# pixracer_imu.net
KiCad netlist of a schematic drawn in Altium Designer
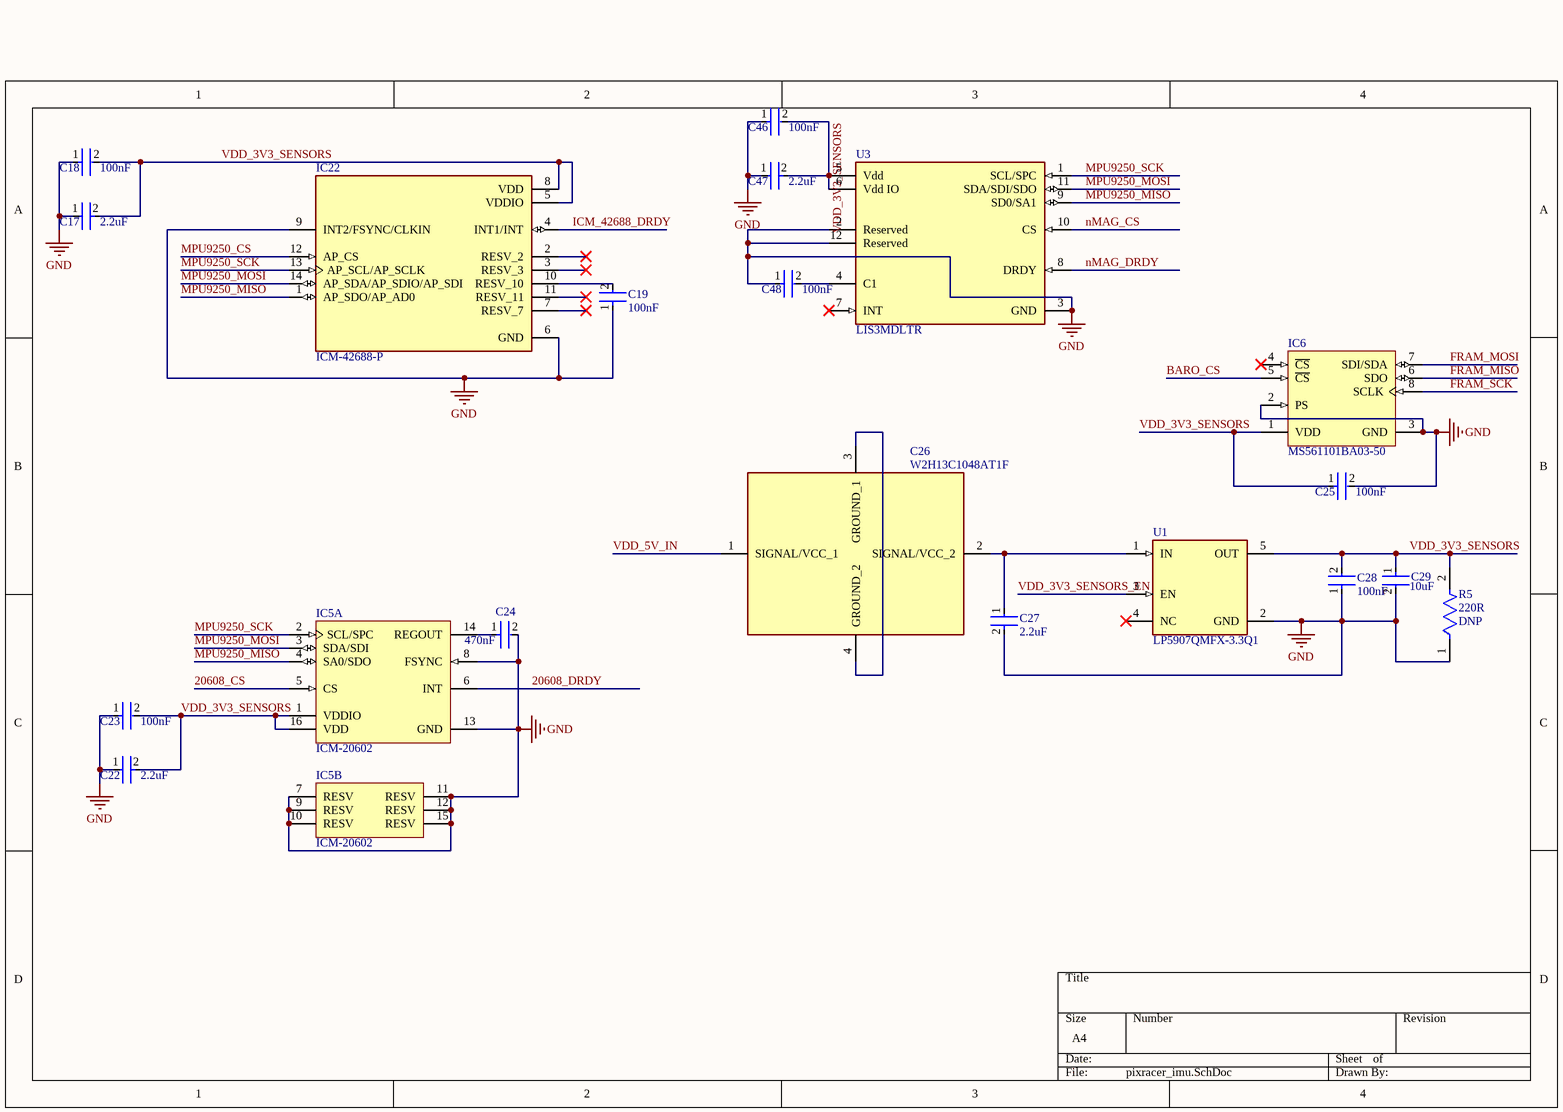
[diagram p0: pixracer_imu.SchDoc]

(export (version "E")
  (design (tool "Eeschema 10.0.6"))
  (components
    (comp (ref "C17")
      (value "C1608X7R1A225K080AC")
      (footprint "FP-C1608-080-0_1-MFG")
      (description "Multilayer Ceramic Capacitors 2.2μF ±10% 10V X7R SMD 0603")
      (fields (field (name "CAPACITANCE") "2.2uF") (field (name "TOLERANCE") "10%"))
      (libsource (lib "Altium Content Vault") (part "236180d848d6139a670b325ea6854c9"))
    )
    (comp (ref "C18")
      (value "0603ZC104MAT2A")
      (footprint "FP-0603-L_1_6_0_15-W_0_81-IPC_B")
      (description "General Purpose Ceramic Capacitor, 0603, 100nF, 20%, X7R, 15%, 10V")
      (fields (field (name "TOLERANCE") "20%") (field (name "CAPACITANCE") "100nF"))
      (libsource (lib "Altium Content Vault") (part "02cd4be3c70576c341d710602a673aa"))
    )
    (comp (ref "C19")
      (value "0603ZC104MAT2A")
      (footprint "FP-0603-L_1_6_0_15-W_0_81-IPC_B")
      (description "General Purpose Ceramic Capacitor, 0603, 100nF, 20%, X7R, 15%, 10V")
      (fields (field (name "TOLERANCE") "20%") (field (name "CAPACITANCE") "100nF"))
      (libsource (lib "Altium Content Vault") (part "02cd4be3c70576c341d710602a673aa"))
    )
    (comp (ref "C22")
      (value "C1608X7R1A225K080AC")
      (footprint "FP-C1608-080-0_1-MFG")
      (description "Multilayer Ceramic Capacitors 2.2μF ±10% 10V X7R SMD 0603")
      (fields (field (name "CAPACITANCE") "2.2uF") (field (name "TOLERANCE") "10%"))
      (libsource (lib "Altium Content Vault") (part "236180d848d6139a670b325ea6854c9"))
    )
    (comp (ref "C23")
      (value "0603ZC104MAT2A")
      (footprint "FP-0603-L_1_6_0_15-W_0_81-IPC_B")
      (description "General Purpose Ceramic Capacitor, 0603, 100nF, 20%, X7R, 15%, 10V")
      (fields (field (name "TOLERANCE") "20%") (field (name "CAPACITANCE") "100nF"))
      (libsource (lib "Altium Content Vault") (part "02cd4be3c70576c341d710602a673aa"))
    )
    (comp (ref "C24")
      (value "CL10B474KP8NNNC")
      (footprint "FP-CL10-IPC_B")
      (description "Cap Ceramic 470nF 10V X7R ±10% Pad SMD 0603 +125°C T/R")
      (fields
        (field (name "VOLTAGE") "10V")
        (field (name "CAPACITANCE") "470nF")
        (field (name "TOLERANCE") "10%")
      )
      (libsource (lib "Altium Content Vault") (part "b4654b650e69147ec39a6b967a45e02"))
    )
    (comp (ref "C25")
      (value "0603ZC104MAT2A")
      (footprint "FP-0603-L_1_6_0_15-W_0_81-IPC_B")
      (description "General Purpose Ceramic Capacitor, 0603, 100nF, 20%, X7R, 15%, 10V")
      (fields (field (name "TOLERANCE") "20%") (field (name "CAPACITANCE") "100nF"))
      (libsource (lib "Altium Content Vault") (part "02cd4be3c70576c341d710602a673aa"))
    )
    (comp (ref "C26")
      (value "W2H13C1048AT1F")
      (footprint "SamacSys:W2H13C1048AT1A")
      (description "Capacitor")
      (fields (field (name "MOUSER PART NUMBER") "581-W2H13C1048AT1F"))
      (libsource (lib "*") (part "W2H13C1048AT1F"))
    )
    (comp (ref "C27")
      (value "C1608X7R1A225K080AC")
      (footprint "FP-C1608-080-0_1-MFG")
      (description "Multilayer Ceramic Capacitors 2.2μF ±10% 10V X7R SMD 0603")
      (fields (field (name "CAPACITANCE") "2.2uF") (field (name "TOLERANCE") "10%"))
      (libsource (lib "Altium Content Vault") (part "236180d848d6139a670b325ea6854c9"))
    )
    (comp (ref "C28")
      (value "0603ZC104MAT2A")
      (footprint "FP-0603-L_1_6_0_15-W_0_81-IPC_B")
      (description "General Purpose Ceramic Capacitor, 0603, 100nF, 20%, X7R, 15%, 10V")
      (fields (field (name "TOLERANCE") "20%") (field (name "CAPACITANCE") "100nF"))
      (libsource (lib "Altium Content Vault") (part "02cd4be3c70576c341d710602a673aa"))
    )
    (comp (ref "C29")
      (value "CL10A106KP8NNND")
      (footprint "FP-CL10-IPC_B")
      (description "Cap Ceramic 10uF 10V X5R ±10% Pad SMD 0603 +85°C T/R")
      (fields (field (name "TOLERANCE") "10%") (field (name "CAPACITANCE") "10uF"))
      (libsource (lib "Altium Content Vault") (part "b4654b650e69147ec39a6b967a45e02"))
    )
    (comp (ref "C46")
      (value "0603ZC104MAT2A")
      (footprint "FP-0603-L_1_6_0_15-W_0_81-IPC_B")
      (description "General Purpose Ceramic Capacitor, 0603, 100nF, 20%, X7R, 15%, 10V")
      (fields (field (name "TOLERANCE") "20%") (field (name "CAPACITANCE") "100nF"))
      (libsource (lib "Altium Content Vault") (part "02cd4be3c70576c341d710602a673aa"))
    )
    (comp (ref "C47")
      (value "C1608X7R1A225K080AC")
      (footprint "FP-C1608-080-0_1-MFG")
      (description "Multilayer Ceramic Capacitors 2.2μF ±10% 10V X7R SMD 0603")
      (fields (field (name "CAPACITANCE") "2.2uF") (field (name "TOLERANCE") "10%"))
      (libsource (lib "Altium Content Vault") (part "236180d848d6139a670b325ea6854c9"))
    )
    (comp (ref "C48")
      (value "0603ZC104MAT2A")
      (footprint "FP-0603-L_1_6_0_15-W_0_81-IPC_B")
      (description "General Purpose Ceramic Capacitor, 0603, 100nF, 20%, X7R, 15%, 10V")
      (fields (field (name "TOLERANCE") "20%") (field (name "CAPACITANCE") "100nF"))
      (libsource (lib "Altium Content Vault") (part "02cd4be3c70576c341d710602a673aa"))
    )
    (comp (ref "IC5")
      (value "ICM-20602")
      (footprint "INSE-I62-16")
      (fields (field (name "MANUFACTURER") "InvenSense"))
      (libsource (lib "Altium Content Vault") (part "INSE-ICM-20602-16"))
    )
    (comp (ref "IC6")
      (value "MS561101BA03-50")
      (footprint "MSI-MS561101BA03-50-8_V")
      (fields (field (name "MANUFACTURER") "Measurement Specialties"))
      (libsource (lib "Altium Content Vault") (part "MSI-MS561101BA03-50-8"))
    )
    (comp (ref "IC22")
      (value "ICM-42688-P")
      (footprint "PQFN50P300X250X97-14N")
      (description "Accelerometer, Gyroscope, 6 Axis Sensor Output")
      (libsource (lib "ICM-42688-P") (part "ICM-42688-P"))
    )
    (comp (ref "R5")
      (value "DNP")
      (footprint "FP-CRCW0603-e3-MFG")
      (description "RES Thick Film, 220Ω, 1%, 0.1W, 100ppm/°C, 0603")
      (fields (field (name "TOLERANCE") "1%") (field (name "RESISTANCE") "220R"))
      (libsource (lib "Altium Content Vault") (part "1029c3af85768c4190bb7ad29bc67b5"))
    )
    (comp (ref "U1")
      (value "LP5907QMFX-3.3Q1")
      (footprint "FP-DBV0005A-MFG")
      (description "IC REG LINEAR 3.3V 250MA SOT23-5")
      (fields
        (field (name "MANUFACTURER") "Texas Instruments")
        (field (name "OCTOPART") "https://octopart.com/lp5907qmfx-3.3q1-texas+instruments-50417899")
      )
      (libsource (lib "Altium Content Vault") (part "e6eddeb8bab6a4ee265087e5808ab9f"))
    )
    (comp (ref "U3")
      (value "LIS3MDLTR")
      (footprint "FP-VFLGA-12-8365767-MFG")
      (description "SENSOR MR I2C/SPI 12LGA")
      (fields
        (field (name "OCTOPART") "https://octopart.com/lis3mdltr-stmicroelectronics-29403125")
        (field (name "MANUFACTURER") "STMicroelectronics")
      )
      (libsource (lib "Altium Content Vault") (part "41c0331d4207a07573b21020ef49d7d"))
    )
  )
  (nets
    (net (code "1") (name "/20608_CS") (class "Default")
      (node (ref "IC5") (pin "5") (pinfunction "CS_5") (pintype "input"))
    )
    (net (code "2") (name "/20608_DRDY") (class "Default")
      (node (ref "IC5") (pin "6") (pinfunction "INT_6") (pintype "open_collector"))
    )
    (net (code "3") (name "/BARO_CS") (class "Default")
      (node (ref "IC6") (pin "5") (pinfunction "~{CS}_5") (pintype "input"))
    )
    (net (code "4") (name "/FRAM_MISO") (class "Default")
      (node (ref "IC6") (pin "6") (pinfunction "SDO_6") (pintype "bidirectional"))
    )
    (net (code "5") (name "/FRAM_MOSI") (class "Default")
      (node (ref "IC6") (pin "7") (pinfunction "SDI/SDA_7") (pintype "bidirectional"))
    )
    (net (code "6") (name "/FRAM_SCK") (class "Default")
      (node (ref "IC6") (pin "8") (pinfunction "SCLK_8") (pintype "input"))
    )
    (net (code "7") (name "/ICM_42688_DRDY") (class "Default")
      (node (ref "IC22") (pin "4") (pinfunction "INT1/INT_4") (pintype "bidirectional"))
    )
    (net (code "8") (name "/MPU9250_CS") (class "Default")
      (node (ref "IC22") (pin "12") (pinfunction "AP_CS_12") (pintype "input"))
    )
    (net (code "9") (name "/MPU9250_MISO") (class "Default")
      (node (ref "IC22") (pin "1") (pinfunction "AP_SDO/AP_AD0_1") (pintype "bidirectional"))
      (node (ref "IC5") (pin "4") (pinfunction "SA0/SDO_4") (pintype "bidirectional"))
      (node (ref "U3") (pin "9") (pinfunction "SD0/SA1_9") (pintype "bidirectional"))
    )
    (net (code "10") (name "/MPU9250_MOSI") (class "Default")
      (node (ref "IC22") (pin "14") (pinfunction "AP_SDA/AP_SDIO/AP_SDI_14") (pintype "bidirectional"))
      (node (ref "IC5") (pin "3") (pinfunction "SDA/SDI_3") (pintype "bidirectional"))
      (node (ref "U3") (pin "11") (pinfunction "SDA/SDI/SDO_11") (pintype "bidirectional"))
    )
    (net (code "11") (name "/MPU9250_SCK") (class "Default")
      (node (ref "IC22") (pin "13") (pinfunction "AP_SCL/AP_SCLK_13") (pintype "input"))
      (node (ref "IC5") (pin "2") (pinfunction "SCL/SPC_2") (pintype "input"))
      (node (ref "U3") (pin "1") (pinfunction "SCL/SPC_1") (pintype "input"))
    )
    (net (code "12") (name "/VDD_3V3_SENSORS") (class "Default")
      (node (ref "C17") (pin "2") (pinfunction "2_2") (pintype "passive"))
      (node (ref "C18") (pin "2") (pinfunction "2_2") (pintype "passive"))
      (node (ref "C22") (pin "2") (pinfunction "2_2") (pintype "passive"))
      (node (ref "C23") (pin "2") (pinfunction "2_2") (pintype "passive"))
      (node (ref "C25") (pin "1") (pinfunction "1_1") (pintype "passive"))
      (node (ref "C28") (pin "2") (pinfunction "2_2") (pintype "passive"))
      (node (ref "C29") (pin "1") (pinfunction "1_1") (pintype "passive"))
      (node (ref "C46") (pin "2") (pinfunction "2_2") (pintype "passive"))
      (node (ref "C47") (pin "2") (pinfunction "2_2") (pintype "passive"))
      (node (ref "IC22") (pin "5") (pinfunction "VDDIO_5") (pintype "passive"))
      (node (ref "IC22") (pin "8") (pinfunction "VDD_8") (pintype "passive"))
      (node (ref "IC5") (pin "1") (pinfunction "VDDIO_1") (pintype "power_in"))
      (node (ref "IC5") (pin "16") (pinfunction "VDD_16") (pintype "power_in"))
      (node (ref "IC6") (pin "1") (pinfunction "VDD_1") (pintype "power_in"))
      (node (ref "R5") (pin "2") (pinfunction "2_2") (pintype "passive"))
      (node (ref "U1") (pin "5") (pinfunction "OUT_5") (pintype "power_in"))
      (node (ref "U3") (pin "5") (pinfunction "Vdd_5") (pintype "power_in"))
      (node (ref "U3") (pin "6") (pinfunction "Vdd_IO_6") (pintype "power_in"))
    )
    (net (code "13") (name "/VDD_3V3_SENSORS_EN") (class "Default")
      (node (ref "U1") (pin "3") (pinfunction "EN_3") (pintype "input"))
    )
    (net (code "14") (name "/VDD_5V_IN") (class "Default")
      (node (ref "C26") (pin "1") (pinfunction "SIGNAL/VCC_1_1") (pintype "passive"))
    )
    (net (code "15") (name "/nMAG_CS") (class "Default")
      (node (ref "U3") (pin "10") (pinfunction "CS_10") (pintype "input"))
    )
    (net (code "16") (name "/nMAG_DRDY") (class "Default")
      (node (ref "U3") (pin "8") (pinfunction "DRDY_8") (pintype "input"))
    )
    (net (code "17") (name "GND") (class "Default")
      (node (ref "C17") (pin "1") (pinfunction "1_1") (pintype "passive"))
      (node (ref "C18") (pin "1") (pinfunction "1_1") (pintype "passive"))
      (node (ref "C19") (pin "1") (pinfunction "1_1") (pintype "passive"))
      (node (ref "C22") (pin "1") (pinfunction "1_1") (pintype "passive"))
      (node (ref "C23") (pin "1") (pinfunction "1_1") (pintype "passive"))
      (node (ref "C24") (pin "2") (pinfunction "2_2") (pintype "passive"))
      (node (ref "C25") (pin "2") (pinfunction "2_2") (pintype "passive"))
      (node (ref "C27") (pin "2") (pinfunction "2_2") (pintype "passive"))
      (node (ref "C28") (pin "1") (pinfunction "1_1") (pintype "passive"))
      (node (ref "C29") (pin "2") (pinfunction "2_2") (pintype "passive"))
      (node (ref "C46") (pin "1") (pinfunction "1_1") (pintype "passive"))
      (node (ref "C47") (pin "1") (pinfunction "1_1") (pintype "passive"))
      (node (ref "C48") (pin "1") (pinfunction "1_1") (pintype "passive"))
      (node (ref "IC22") (pin "6") (pinfunction "GND_6") (pintype "passive"))
      (node (ref "IC22") (pin "9") (pinfunction "INT2/FSYNC/CLKIN_9") (pintype "passive"))
      (node (ref "IC5") (pin "10") (pinfunction "RESV_10") (pintype "passive"))
      (node (ref "IC5") (pin "11") (pinfunction "RESV_11") (pintype "passive"))
      (node (ref "IC5") (pin "12") (pinfunction "RESV_12") (pintype "passive"))
      (node (ref "IC5") (pin "13") (pinfunction "GND_13") (pintype "power_in"))
      (node (ref "IC5") (pin "15") (pinfunction "RESV_15") (pintype "passive"))
      (node (ref "IC5") (pin "7") (pinfunction "RESV_7") (pintype "passive"))
      (node (ref "IC5") (pin "8") (pinfunction "FSYNC_8") (pintype "input"))
      (node (ref "IC5") (pin "9") (pinfunction "RESV_9") (pintype "passive"))
      (node (ref "IC6") (pin "2") (pinfunction "PS_2") (pintype "input"))
      (node (ref "IC6") (pin "3") (pinfunction "GND_3") (pintype "power_in"))
      (node (ref "R5") (pin "1") (pinfunction "1_1") (pintype "passive"))
      (node (ref "U1") (pin "2") (pinfunction "GND_2") (pintype "power_in"))
      (node (ref "U3") (pin "12") (pinfunction "Reserved_12") (pintype "passive"))
      (node (ref "U3") (pin "2") (pinfunction "Reserved_2") (pintype "passive"))
      (node (ref "U3") (pin "3") (pinfunction "GND_3") (pintype "power_in"))
    )
    (net (code "18") (name "Net-(C26-GROUND_1)") (class "Default")
      (node (ref "C26") (pin "3") (pinfunction "GROUND_1_3") (pintype "passive"))
      (node (ref "C26") (pin "4") (pinfunction "GROUND_2_4") (pintype "passive"))
    )
    (net (code "19") (name "Net-(C26-SIGNAL{slash}VCC_2)") (class "Default")
      (node (ref "C26") (pin "2") (pinfunction "SIGNAL/VCC_2_2") (pintype "passive"))
      (node (ref "C27") (pin "1") (pinfunction "1_1") (pintype "passive"))
      (node (ref "U1") (pin "1") (pinfunction "IN_1") (pintype "input"))
    )
    (net (code "20") (name "Net-(IC5A-REGOUT)") (class "Default")
      (node (ref "C24") (pin "1") (pinfunction "1_1") (pintype "passive"))
      (node (ref "IC5") (pin "14") (pinfunction "REGOUT_14") (pintype "passive"))
    )
    (net (code "21") (name "Net-(IC22-RESV_10)") (class "Default")
      (node (ref "C19") (pin "2") (pinfunction "2_2") (pintype "passive"))
      (node (ref "IC22") (pin "10") (pinfunction "RESV_10_10") (pintype "passive"))
    )
    (net (code "22") (name "Net-(U3-C1)") (class "Default")
      (node (ref "C48") (pin "2") (pinfunction "2_2") (pintype "passive"))
      (node (ref "U3") (pin "4") (pinfunction "C1_4") (pintype "passive"))
    )
    (net (code "23") (name "unconnected-(IC6-~{CS}-Pad4)") (class "Default")
      (node (ref "IC6") (pin "4") (pinfunction "~{CS}_4") (pintype "input+no_connect"))
    )
    (net (code "24") (name "unconnected-(IC22-RESV_2-Pad2)") (class "Default")
      (node (ref "IC22") (pin "2") (pinfunction "RESV_2_2") (pintype "passive+no_connect"))
    )
    (net (code "25") (name "unconnected-(IC22-RESV_3-Pad3)") (class "Default")
      (node (ref "IC22") (pin "3") (pinfunction "RESV_3_3") (pintype "passive+no_connect"))
    )
    (net (code "26") (name "unconnected-(IC22-RESV_7-Pad7)") (class "Default")
      (node (ref "IC22") (pin "7") (pinfunction "RESV_7_7") (pintype "passive+no_connect"))
    )
    (net (code "27") (name "unconnected-(IC22-RESV_11-Pad11)") (class "Default")
      (node (ref "IC22") (pin "11") (pinfunction "RESV_11_11") (pintype "passive+no_connect"))
    )
    (net (code "28") (name "unconnected-(U1-NC-Pad4)") (class "Default")
      (node (ref "U1") (pin "4") (pinfunction "NC_4") (pintype "passive+no_connect"))
    )
    (net (code "29") (name "unconnected-(U3-INT-Pad7)") (class "Default")
      (node (ref "U3") (pin "7") (pinfunction "INT_7") (pintype "input+no_connect"))
    )
  )
)
